# pwm-555.net
KiCad netlist of a schematic drawn in EAGLE
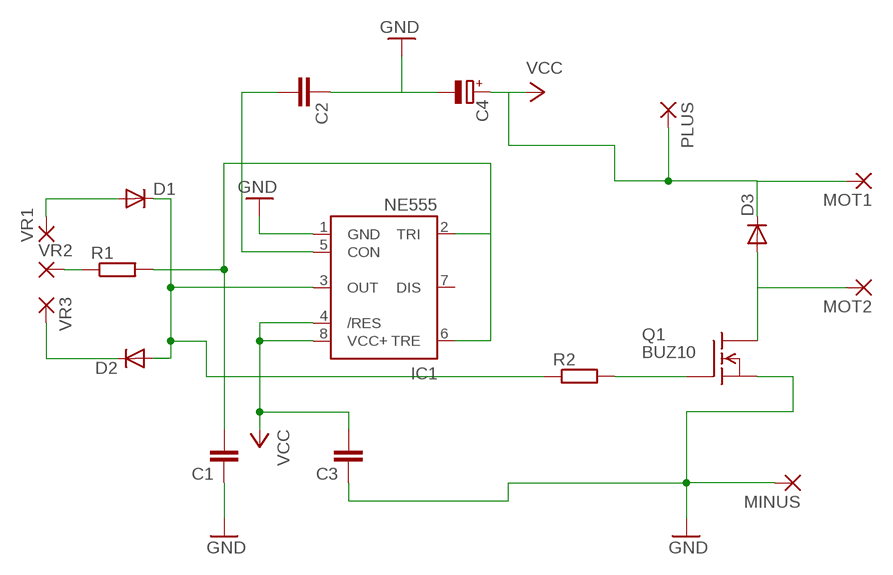
[diagram p0: schematic, sheet 1]

(export (version "E")
  (design (tool "Eeschema 10.0.6"))
  (components
    (comp (ref "C1")
      (value "C-EU050-030X075")
      (footprint "eagle-import:C050-030X075")
      (libsource (lib "eagle-import") (part "C-EU050-030X075"))
    )
    (comp (ref "C2")
      (value "C-EU050-030X075")
      (footprint "eagle-import:C050-030X075")
      (libsource (lib "eagle-import") (part "C-EU050-030X075"))
    )
    (comp (ref "C3")
      (value "C-EU050-030X075")
      (footprint "eagle-import:C050-030X075")
      (libsource (lib "eagle-import") (part "C-EU050-030X075"))
    )
    (comp (ref "C4")
      (value "CPOL-EUE2-5")
      (footprint "eagle-import:E2-5")
      (libsource (lib "eagle-import") (part "CPOL-EUE2-5"))
    )
    (comp (ref "D1")
      (value "DIODE-D-7.5")
      (footprint "eagle-import:D-7.5")
      (libsource (lib "eagle-import") (part "DIODE-D-7.5"))
    )
    (comp (ref "D2")
      (value "DIODE-D-7.5")
      (footprint "eagle-import:D-7.5")
      (libsource (lib "eagle-import") (part "DIODE-D-7.5"))
    )
    (comp (ref "D3")
      (value "DIODE-D-7.5")
      (footprint "eagle-import:D-7.5")
      (libsource (lib "eagle-import") (part "DIODE-D-7.5"))
    )
    (comp (ref "IC1")
      (value "NE555")
      (footprint "eagle-import:DIL-08")
      (fields (field (name "MF") "Arrow Electronics") (field (name "MPN") "NE555N"))
      (libsource (lib "eagle-import") (part "NE555"))
    )
    (comp (ref "MINUS")
      (value "2,54/0,9")
      (footprint "eagle-import:2,54_0,9")
      (libsource (lib "eagle-import") (part "2,54/0,9"))
    )
    (comp (ref "MOT1")
      (value "2,54/0,9")
      (footprint "eagle-import:2,54_0,9")
      (libsource (lib "eagle-import") (part "2,54/0,9"))
    )
    (comp (ref "MOT2")
      (value "2,54/0,9")
      (footprint "eagle-import:2,54_0,9")
      (libsource (lib "eagle-import") (part "2,54/0,9"))
    )
    (comp (ref "PLUS")
      (value "2,54/0,9")
      (footprint "eagle-import:2,54_0,9")
      (libsource (lib "eagle-import") (part "2,54/0,9"))
    )
    (comp (ref "Q1")
      (value "BUZ10")
      (footprint "eagle-import:TO220")
      (libsource (lib "eagle-import") (part "BUZ10"))
    )
    (comp (ref "R1")
      (value "R-EU_0204/7")
      (footprint "eagle-import:0204_7")
      (libsource (lib "eagle-import") (part "R-EU_0204/7"))
    )
    (comp (ref "R2")
      (value "R-EU_0204/7")
      (footprint "eagle-import:0204_7")
      (libsource (lib "eagle-import") (part "R-EU_0204/7"))
    )
    (comp (ref "VR1")
      (value "2,54/0,9")
      (footprint "eagle-import:2,54_0,9")
      (libsource (lib "eagle-import") (part "2,54/0,9"))
    )
    (comp (ref "VR2")
      (value "2,54/0,9")
      (footprint "eagle-import:2,54_0,9")
      (libsource (lib "eagle-import") (part "2,54/0,9"))
    )
    (comp (ref "VR3")
      (value "2,54/0,9")
      (footprint "eagle-import:2,54_0,9")
      (libsource (lib "eagle-import") (part "2,54/0,9"))
    )
  )
  (nets
    (net (code "1") (name "GND") (class "Default")
      (node (ref "C1") (pin "1") (pinfunction "1_1") (pintype "passive"))
      (node (ref "C2") (pin "1") (pinfunction "1_1") (pintype "passive"))
      (node (ref "C3") (pin "1") (pinfunction "1_1") (pintype "passive"))
      (node (ref "C4") (pin "-") (pinfunction "-_-") (pintype "passive"))
      (node (ref "IC1") (pin "1") (pinfunction "GND_1") (pintype "power_in"))
      (node (ref "MINUS") (pin "1") (pinfunction "P_1") (pintype "passive"))
      (node (ref "Q1") (pin "3") (pinfunction "S_3") (pintype "passive"))
    )
    (net (code "2") (name "Net-(IC1-CON)") (class "Default")
      (node (ref "C2") (pin "2") (pinfunction "2_2") (pintype "passive"))
      (node (ref "IC1") (pin "5") (pinfunction "CON_5") (pintype "input"))
    )
    (net (code "3") (name "Net-(IC1-OUT)") (class "Default")
      (node (ref "D1") (pin "C") (pinfunction "C_C") (pintype "passive"))
      (node (ref "D2") (pin "A") (pinfunction "A_A") (pintype "passive"))
      (node (ref "IC1") (pin "3") (pinfunction "OUT_3") (pintype "output"))
      (node (ref "R2") (pin "1") (pinfunction "1_1") (pintype "passive"))
    )
    (net (code "4") (name "Net-(IC1-TRE)") (class "Default")
      (node (ref "C1") (pin "2") (pinfunction "2_2") (pintype "passive"))
      (node (ref "IC1") (pin "2") (pinfunction "TRI_2") (pintype "input"))
      (node (ref "IC1") (pin "6") (pinfunction "TRE_6") (pintype "input"))
      (node (ref "R1") (pin "2") (pinfunction "2_2") (pintype "passive"))
    )
    (net (code "5") (name "Net-(MOT2-P)") (class "Default")
      (node (ref "D3") (pin "A") (pinfunction "A_A") (pintype "passive"))
      (node (ref "MOT2") (pin "1") (pinfunction "P_1") (pintype "passive"))
      (node (ref "Q1") (pin "2") (pinfunction "D_2") (pintype "passive"))
    )
    (net (code "6") (name "Net-(Q1-G)") (class "Default")
      (node (ref "Q1") (pin "1") (pinfunction "G_1") (pintype "passive"))
      (node (ref "R2") (pin "2") (pinfunction "2_2") (pintype "passive"))
    )
    (net (code "7") (name "Net-(VR1-P)") (class "Default")
      (node (ref "D1") (pin "A") (pinfunction "A_A") (pintype "passive"))
      (node (ref "VR1") (pin "1") (pinfunction "P_1") (pintype "passive"))
    )
    (net (code "8") (name "Net-(VR2-P)") (class "Default")
      (node (ref "R1") (pin "1") (pinfunction "1_1") (pintype "passive"))
      (node (ref "VR2") (pin "1") (pinfunction "P_1") (pintype "passive"))
    )
    (net (code "9") (name "Net-(VR3-P)") (class "Default")
      (node (ref "D2") (pin "C") (pinfunction "C_C") (pintype "passive"))
      (node (ref "VR3") (pin "1") (pinfunction "P_1") (pintype "passive"))
    )
    (net (code "10") (name "VCC") (class "Default")
      (node (ref "C3") (pin "2") (pinfunction "2_2") (pintype "passive"))
      (node (ref "C4") (pin "+") (pinfunction "+_+") (pintype "passive"))
      (node (ref "D3") (pin "C") (pinfunction "C_C") (pintype "passive"))
      (node (ref "IC1") (pin "4") (pinfunction "/RES_4") (pintype "input"))
      (node (ref "IC1") (pin "8") (pinfunction "VCC+_8") (pintype "power_in"))
      (node (ref "MOT1") (pin "1") (pinfunction "P_1") (pintype "passive"))
      (node (ref "PLUS") (pin "1") (pinfunction "P_1") (pintype "passive"))
    )
    (net (code "11") (name "unconnected-(IC1-DIS-Pad7)") (class "Default")
      (node (ref "IC1") (pin "7") (pinfunction "DIS_7") (pintype "input"))
    )
  )
)
